# Octal_Transceiver_Breakout.net
KiCad netlist of a schematic drawn in EAGLE
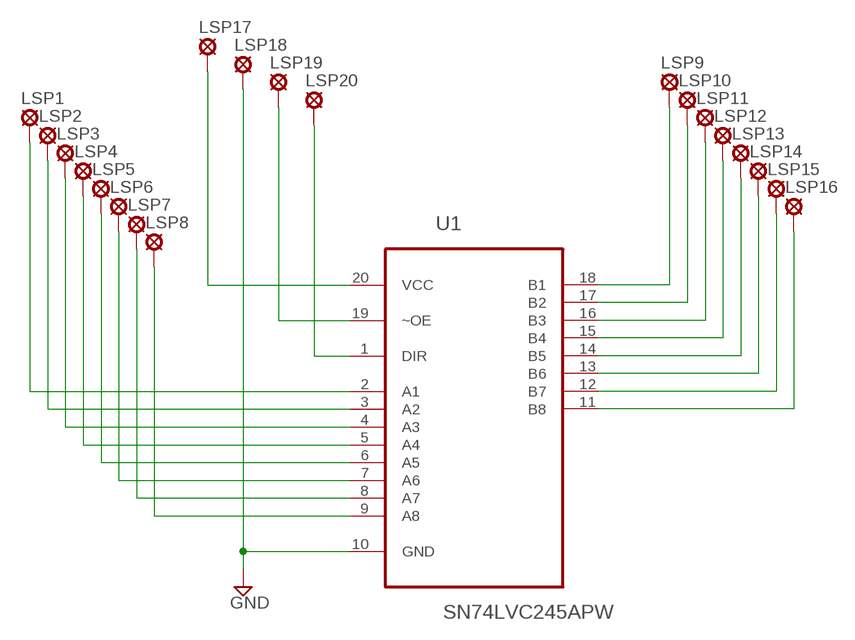
[diagram p0: schematic, sheet 1]

(export (version "E")
  (design (tool "Eeschema 10.0.6"))
  (components
    (comp (ref "LSP1")
      (value "LSP10_CLSP10_C")
      (footprint "eagle-import:LSP10_C")
      (libsource (lib "eagle-import") (part "LSP10_CLSP10_C"))
    )
    (comp (ref "LSP2")
      (value "LSP10_CLSP10_C")
      (footprint "eagle-import:LSP10_C")
      (libsource (lib "eagle-import") (part "LSP10_CLSP10_C"))
    )
    (comp (ref "LSP3")
      (value "LSP10_CLSP10_C")
      (footprint "eagle-import:LSP10_C")
      (libsource (lib "eagle-import") (part "LSP10_CLSP10_C"))
    )
    (comp (ref "LSP4")
      (value "LSP10_CLSP10_C")
      (footprint "eagle-import:LSP10_C")
      (libsource (lib "eagle-import") (part "LSP10_CLSP10_C"))
    )
    (comp (ref "LSP5")
      (value "LSP10_CLSP10_C")
      (footprint "eagle-import:LSP10_C")
      (libsource (lib "eagle-import") (part "LSP10_CLSP10_C"))
    )
    (comp (ref "LSP6")
      (value "LSP10_CLSP10_C")
      (footprint "eagle-import:LSP10_C")
      (libsource (lib "eagle-import") (part "LSP10_CLSP10_C"))
    )
    (comp (ref "LSP7")
      (value "LSP10_CLSP10_C")
      (footprint "eagle-import:LSP10_C")
      (libsource (lib "eagle-import") (part "LSP10_CLSP10_C"))
    )
    (comp (ref "LSP8")
      (value "LSP10_CLSP10_C")
      (footprint "eagle-import:LSP10_C")
      (libsource (lib "eagle-import") (part "LSP10_CLSP10_C"))
    )
    (comp (ref "LSP9")
      (value "LSP10_CLSP10_C")
      (footprint "eagle-import:LSP10_C")
      (libsource (lib "eagle-import") (part "LSP10_CLSP10_C"))
    )
    (comp (ref "LSP10")
      (value "LSP10_CLSP10_C")
      (footprint "eagle-import:LSP10_C")
      (libsource (lib "eagle-import") (part "LSP10_CLSP10_C"))
    )
    (comp (ref "LSP11")
      (value "LSP10_CLSP10_C")
      (footprint "eagle-import:LSP10_C")
      (libsource (lib "eagle-import") (part "LSP10_CLSP10_C"))
    )
    (comp (ref "LSP12")
      (value "LSP10_CLSP10_C")
      (footprint "eagle-import:LSP10_C")
      (libsource (lib "eagle-import") (part "LSP10_CLSP10_C"))
    )
    (comp (ref "LSP13")
      (value "LSP10_CLSP10_C")
      (footprint "eagle-import:LSP10_C")
      (libsource (lib "eagle-import") (part "LSP10_CLSP10_C"))
    )
    (comp (ref "LSP14")
      (value "LSP10_CLSP10_C")
      (footprint "eagle-import:LSP10_C")
      (libsource (lib "eagle-import") (part "LSP10_CLSP10_C"))
    )
    (comp (ref "LSP15")
      (value "LSP10_CLSP10_C")
      (footprint "eagle-import:LSP10_C")
      (libsource (lib "eagle-import") (part "LSP10_CLSP10_C"))
    )
    (comp (ref "LSP16")
      (value "LSP10_CLSP10_C")
      (footprint "eagle-import:LSP10_C")
      (libsource (lib "eagle-import") (part "LSP10_CLSP10_C"))
    )
    (comp (ref "LSP17")
      (value "LSP10_CLSP10_C")
      (footprint "eagle-import:LSP10_C")
      (libsource (lib "eagle-import") (part "LSP10_CLSP10_C"))
    )
    (comp (ref "LSP18")
      (value "LSP10_CLSP10_C")
      (footprint "eagle-import:LSP10_C")
      (libsource (lib "eagle-import") (part "LSP10_CLSP10_C"))
    )
    (comp (ref "LSP19")
      (value "LSP10_CLSP10_C")
      (footprint "eagle-import:LSP10_C")
      (libsource (lib "eagle-import") (part "LSP10_CLSP10_C"))
    )
    (comp (ref "LSP20")
      (value "LSP10_CLSP10_C")
      (footprint "eagle-import:LSP10_C")
      (libsource (lib "eagle-import") (part "LSP10_CLSP10_C"))
    )
    (comp (ref "U1")
      (value "SN74LVC245APW")
      (footprint "eagle-import:SOP65P640X120-20N")
      (fields (field (name "MF") "Texas Instruments"))
      (libsource (lib "eagle-import") (part "SN74LVC245APW"))
    )
  )
  (nets
    (net (code "1") (name "GND") (class "Default")
      (node (ref "LSP18") (pin "P$1") (pinfunction "MP_P$1") (pintype "passive"))
      (node (ref "U1") (pin "10") (pinfunction "GND_10") (pintype "passive"))
    )
    (net (code "2") (name "Net-(LSP1-MP)") (class "Default")
      (node (ref "LSP1") (pin "P$1") (pinfunction "MP_P$1") (pintype "passive"))
      (node (ref "U1") (pin "2") (pinfunction "A1_2") (pintype "bidirectional"))
    )
    (net (code "3") (name "Net-(LSP2-MP)") (class "Default")
      (node (ref "LSP2") (pin "P$1") (pinfunction "MP_P$1") (pintype "passive"))
      (node (ref "U1") (pin "3") (pinfunction "A2_3") (pintype "bidirectional"))
    )
    (net (code "4") (name "Net-(LSP3-MP)") (class "Default")
      (node (ref "LSP3") (pin "P$1") (pinfunction "MP_P$1") (pintype "passive"))
      (node (ref "U1") (pin "4") (pinfunction "A3_4") (pintype "bidirectional"))
    )
    (net (code "5") (name "Net-(LSP4-MP)") (class "Default")
      (node (ref "LSP4") (pin "P$1") (pinfunction "MP_P$1") (pintype "passive"))
      (node (ref "U1") (pin "5") (pinfunction "A4_5") (pintype "bidirectional"))
    )
    (net (code "6") (name "Net-(LSP5-MP)") (class "Default")
      (node (ref "LSP5") (pin "P$1") (pinfunction "MP_P$1") (pintype "passive"))
      (node (ref "U1") (pin "6") (pinfunction "A5_6") (pintype "bidirectional"))
    )
    (net (code "7") (name "Net-(LSP6-MP)") (class "Default")
      (node (ref "LSP6") (pin "P$1") (pinfunction "MP_P$1") (pintype "passive"))
      (node (ref "U1") (pin "7") (pinfunction "A6_7") (pintype "bidirectional"))
    )
    (net (code "8") (name "Net-(LSP7-MP)") (class "Default")
      (node (ref "LSP7") (pin "P$1") (pinfunction "MP_P$1") (pintype "passive"))
      (node (ref "U1") (pin "8") (pinfunction "A7_8") (pintype "bidirectional"))
    )
    (net (code "9") (name "Net-(LSP8-MP)") (class "Default")
      (node (ref "LSP8") (pin "P$1") (pinfunction "MP_P$1") (pintype "passive"))
      (node (ref "U1") (pin "9") (pinfunction "A8_9") (pintype "bidirectional"))
    )
    (net (code "10") (name "Net-(LSP9-MP)") (class "Default")
      (node (ref "LSP9") (pin "P$1") (pinfunction "MP_P$1") (pintype "passive"))
      (node (ref "U1") (pin "18") (pinfunction "B1_18") (pintype "bidirectional"))
    )
    (net (code "11") (name "Net-(LSP10-MP)") (class "Default")
      (node (ref "LSP10") (pin "P$1") (pinfunction "MP_P$1") (pintype "passive"))
      (node (ref "U1") (pin "17") (pinfunction "B2_17") (pintype "bidirectional"))
    )
    (net (code "12") (name "Net-(LSP11-MP)") (class "Default")
      (node (ref "LSP11") (pin "P$1") (pinfunction "MP_P$1") (pintype "passive"))
      (node (ref "U1") (pin "16") (pinfunction "B3_16") (pintype "bidirectional"))
    )
    (net (code "13") (name "Net-(LSP12-MP)") (class "Default")
      (node (ref "LSP12") (pin "P$1") (pinfunction "MP_P$1") (pintype "passive"))
      (node (ref "U1") (pin "15") (pinfunction "B4_15") (pintype "bidirectional"))
    )
    (net (code "14") (name "Net-(LSP13-MP)") (class "Default")
      (node (ref "LSP13") (pin "P$1") (pinfunction "MP_P$1") (pintype "passive"))
      (node (ref "U1") (pin "14") (pinfunction "B5_14") (pintype "bidirectional"))
    )
    (net (code "15") (name "Net-(LSP14-MP)") (class "Default")
      (node (ref "LSP14") (pin "P$1") (pinfunction "MP_P$1") (pintype "passive"))
      (node (ref "U1") (pin "13") (pinfunction "B6_13") (pintype "bidirectional"))
    )
    (net (code "16") (name "Net-(LSP15-MP)") (class "Default")
      (node (ref "LSP15") (pin "P$1") (pinfunction "MP_P$1") (pintype "passive"))
      (node (ref "U1") (pin "12") (pinfunction "B7_12") (pintype "bidirectional"))
    )
    (net (code "17") (name "Net-(LSP16-MP)") (class "Default")
      (node (ref "LSP16") (pin "P$1") (pinfunction "MP_P$1") (pintype "passive"))
      (node (ref "U1") (pin "11") (pinfunction "B8_11") (pintype "bidirectional"))
    )
    (net (code "18") (name "Net-(LSP17-MP)") (class "Default")
      (node (ref "LSP17") (pin "P$1") (pinfunction "MP_P$1") (pintype "passive"))
      (node (ref "U1") (pin "20") (pinfunction "VCC_20") (pintype "power_in"))
    )
    (net (code "19") (name "Net-(LSP19-MP)") (class "Default")
      (node (ref "LSP19") (pin "P$1") (pinfunction "MP_P$1") (pintype "passive"))
      (node (ref "U1") (pin "19") (pinfunction "~{OE}_19") (pintype "input"))
    )
    (net (code "20") (name "Net-(LSP20-MP)") (class "Default")
      (node (ref "LSP20") (pin "P$1") (pinfunction "MP_P$1") (pintype "passive"))
      (node (ref "U1") (pin "1") (pinfunction "DIR_1") (pintype "input"))
    )
  )
)
